# 555zapis.net
KiCad netlist of a schematic drawn in EAGLE
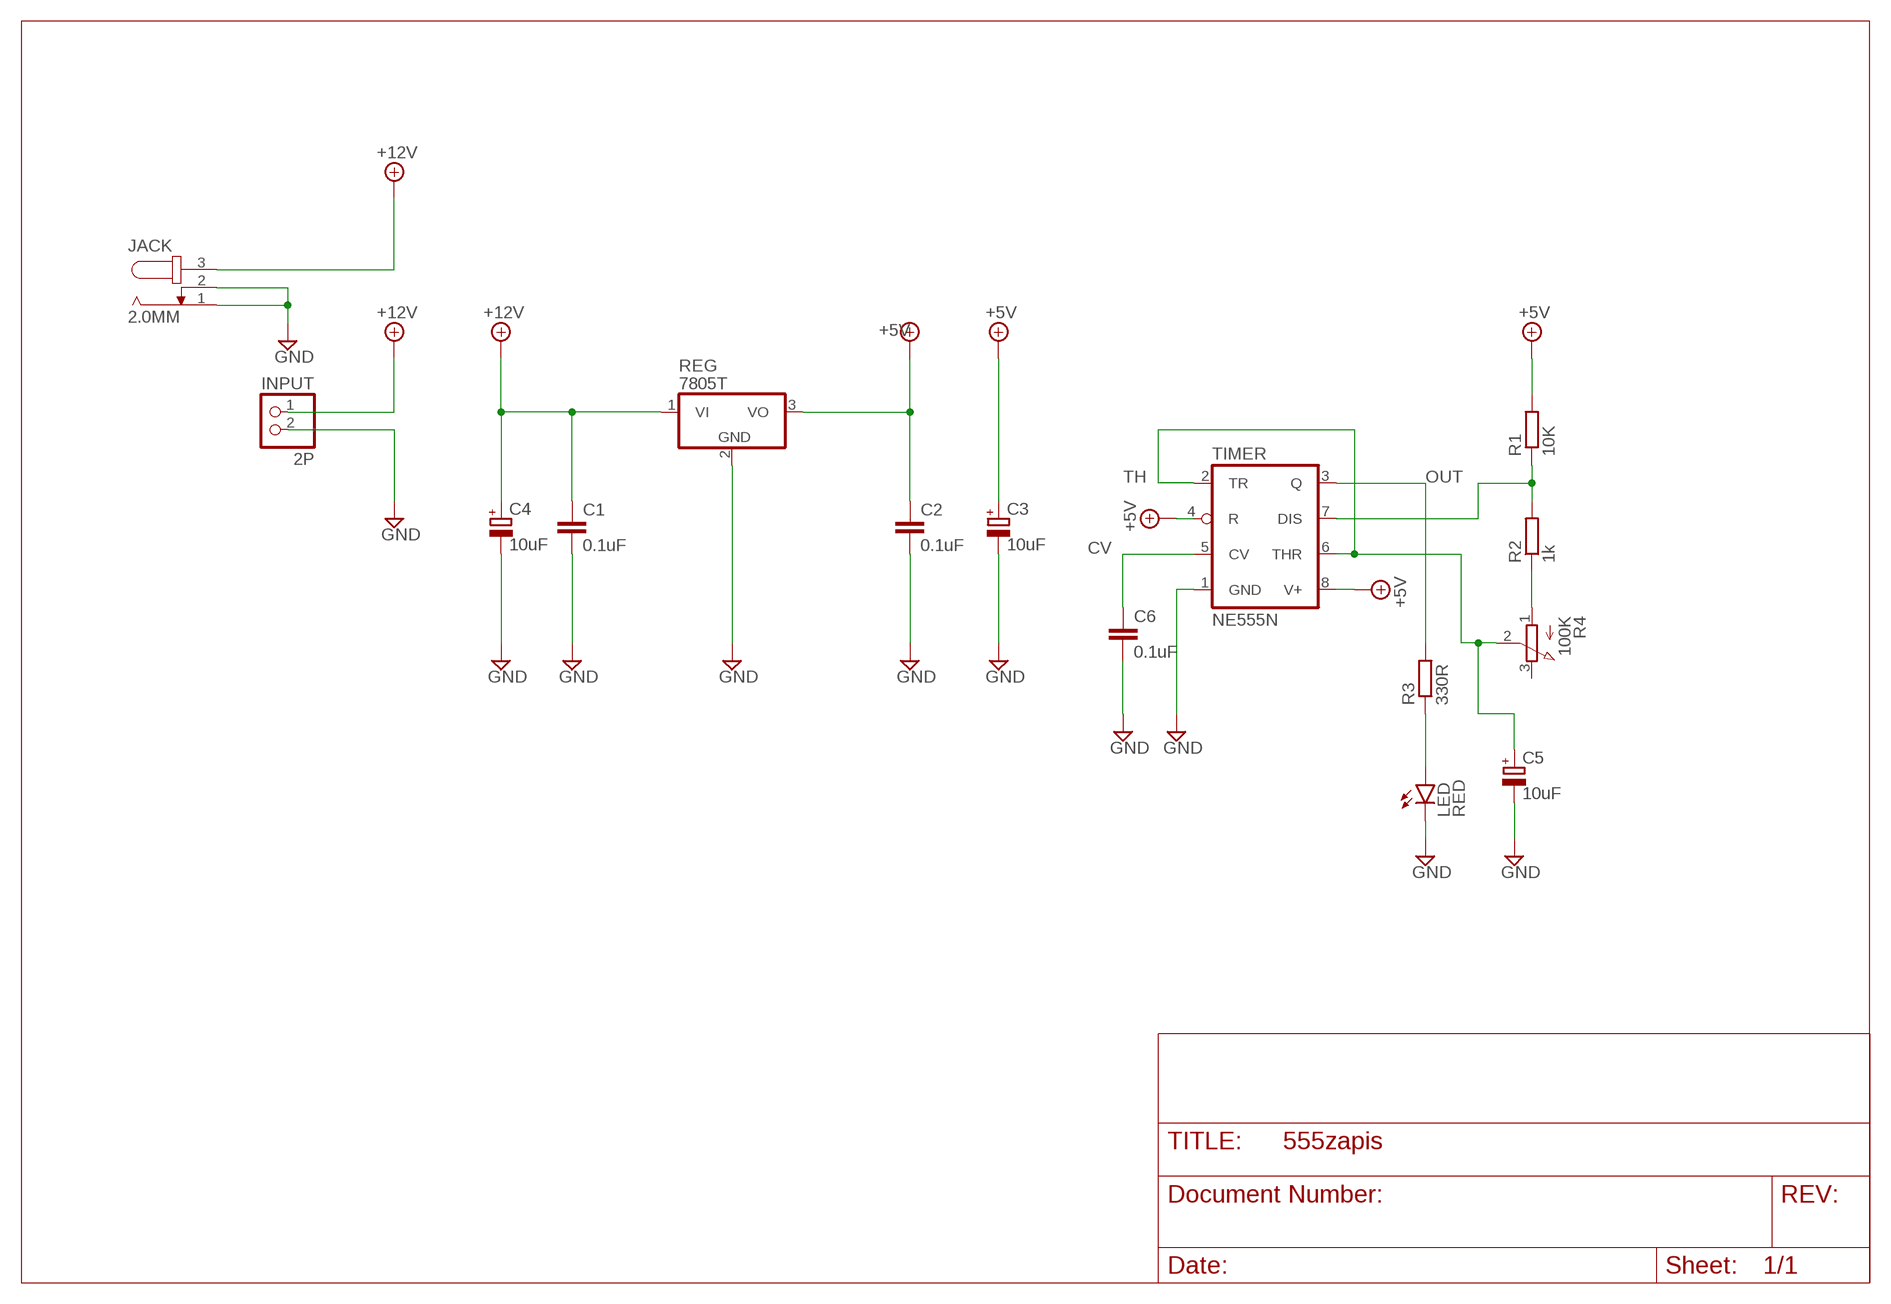
[diagram p0: schematic, sheet 1]

(export (version "E")
  (design (tool "Eeschema 10.0.6"))
  (components
    (comp (ref "C1")
      (value "0.1uF")
      (footprint "eagle-import:C050-030X075")
      (libsource (lib "eagle-import") (part "C-EU050-030X075"))
    )
    (comp (ref "C2")
      (value "0.1uF")
      (footprint "eagle-import:C050-030X075")
      (libsource (lib "eagle-import") (part "C-EU050-030X075"))
    )
    (comp (ref "C3")
      (value "10uF")
      (footprint "eagle-import:E3,5-8")
      (libsource (lib "eagle-import") (part "CPOL-EUE3.5-8"))
    )
    (comp (ref "C4")
      (value "10uF")
      (footprint "eagle-import:E3,5-8")
      (libsource (lib "eagle-import") (part "CPOL-EUE3.5-8"))
    )
    (comp (ref "C5")
      (value "10uF")
      (footprint "eagle-import:E3,5-8")
      (libsource (lib "eagle-import") (part "CPOL-EUE3.5-8"))
    )
    (comp (ref "C6")
      (value "0.1uF")
      (footprint "eagle-import:C050-030X075")
      (libsource (lib "eagle-import") (part "C-EU050-030X075"))
    )
    (comp (ref "INPUT")
      (value "2P")
      (footprint "eagle-import:1X02")
      (libsource (lib "eagle-import") (part "PINHD-1X2"))
    )
    (comp (ref "JACK")
      (value "2.0MM")
      (footprint "eagle-import:SPC4078")
      (libsource (lib "eagle-import") (part "JACK-PLUG1"))
    )
    (comp (ref "LED")
      (value "RED")
      (footprint "eagle-import:LED5MM")
      (libsource (lib "eagle-import") (part "LED5MM"))
    )
    (comp (ref "R1")
      (value "10K")
      (footprint "eagle-import:0207_10")
      (libsource (lib "eagle-import") (part "R-EU_0207/10"))
    )
    (comp (ref "R2")
      (value "1k")
      (footprint "eagle-import:0207_10")
      (libsource (lib "eagle-import") (part "R-EU_0207/10"))
    )
    (comp (ref "R3")
      (value "330R")
      (footprint "eagle-import:0207_10")
      (libsource (lib "eagle-import") (part "R-EU_0207/10"))
    )
    (comp (ref "R4")
      (value "100K")
      (footprint "eagle-import:3RP_1610N")
      (libsource (lib "eagle-import") (part "3RP/1610N"))
    )
    (comp (ref "REG")
      (value "7805T")
      (footprint "eagle-import:TO220H")
      (libsource (lib "eagle-import") (part "78T05"))
    )
    (comp (ref "TIMER")
      (value "NE555N")
      (footprint "eagle-import:DIL08")
      (libsource (lib "eagle-import") (part "555NNE"))
    )
  )
  (nets
    (net (code "1") (name "+5V") (class "Default")
      (node (ref "C2") (pin "1") (pinfunction "1_1") (pintype "passive"))
      (node (ref "C3") (pin "+") (pinfunction "+_+") (pintype "passive"))
      (node (ref "R1") (pin "2") (pinfunction "2_2") (pintype "passive"))
      (node (ref "REG") (pin "3") (pinfunction "VO_3") (pintype "passive"))
      (node (ref "TIMER") (pin "4") (pinfunction "R_4") (pintype "input"))
      (node (ref "TIMER") (pin "8") (pinfunction "V+_8") (pintype "power_in"))
    )
    (net (code "2") (name "+12V") (class "Default")
      (node (ref "C1") (pin "1") (pinfunction "1_1") (pintype "passive"))
      (node (ref "C4") (pin "+") (pinfunction "+_+") (pintype "passive"))
      (node (ref "INPUT") (pin "1") (pinfunction "1_1") (pintype "passive"))
      (node (ref "JACK") (pin "3") (pinfunction "3_3") (pintype "passive"))
      (node (ref "REG") (pin "1") (pinfunction "VI_1") (pintype "input"))
    )
    (net (code "3") (name "/CV") (class "Default")
      (node (ref "C6") (pin "1") (pinfunction "1_1") (pintype "passive"))
      (node (ref "TIMER") (pin "5") (pinfunction "CV_5") (pintype "input"))
    )
    (net (code "4") (name "/OUT") (class "Default")
      (node (ref "R3") (pin "2") (pinfunction "2_2") (pintype "passive"))
      (node (ref "TIMER") (pin "3") (pinfunction "Q_3") (pintype "output"))
    )
    (net (code "5") (name "/TH") (class "Default")
      (node (ref "C5") (pin "+") (pinfunction "+_+") (pintype "passive"))
      (node (ref "R4") (pin "2") (pinfunction "S_2") (pintype "passive"))
      (node (ref "TIMER") (pin "2") (pinfunction "TR_2") (pintype "input"))
      (node (ref "TIMER") (pin "6") (pinfunction "THR_6") (pintype "input"))
    )
    (net (code "6") (name "GND") (class "Default")
      (node (ref "C1") (pin "2") (pinfunction "2_2") (pintype "passive"))
      (node (ref "C2") (pin "2") (pinfunction "2_2") (pintype "passive"))
      (node (ref "C3") (pin "-") (pinfunction "-_-") (pintype "passive"))
      (node (ref "C4") (pin "-") (pinfunction "-_-") (pintype "passive"))
      (node (ref "C5") (pin "-") (pinfunction "-_-") (pintype "passive"))
      (node (ref "C6") (pin "2") (pinfunction "2_2") (pintype "passive"))
      (node (ref "INPUT") (pin "2") (pinfunction "2_2") (pintype "passive"))
      (node (ref "JACK") (pin "1") (pinfunction "1_1") (pintype "passive"))
      (node (ref "JACK") (pin "2") (pinfunction "2_2") (pintype "passive"))
      (node (ref "LED") (pin "K") (pinfunction "C_K") (pintype "passive"))
      (node (ref "REG") (pin "2") (pinfunction "GND_2") (pintype "passive"))
      (node (ref "TIMER") (pin "1") (pinfunction "GND_1") (pintype "power_in"))
    )
    (net (code "7") (name "Net-(LED-PadA)") (class "Default")
      (node (ref "LED") (pin "A") (pinfunction "A_A") (pintype "passive"))
      (node (ref "R3") (pin "1") (pinfunction "1_1") (pintype "passive"))
    )
    (net (code "8") (name "Net-(R4-A)") (class "Default")
      (node (ref "R2") (pin "1") (pinfunction "1_1") (pintype "passive"))
      (node (ref "R4") (pin "1") (pinfunction "A_1") (pintype "passive"))
    )
    (net (code "9") (name "Net-(TIMER-DIS)") (class "Default")
      (node (ref "R1") (pin "1") (pinfunction "1_1") (pintype "passive"))
      (node (ref "R2") (pin "2") (pinfunction "2_2") (pintype "passive"))
      (node (ref "TIMER") (pin "7") (pinfunction "DIS_7") (pintype "input"))
    )
    (net (code "10") (name "unconnected-(R4-E-Pad3)") (class "Default")
      (node (ref "R4") (pin "3") (pinfunction "E_3") (pintype "passive"))
    )
  )
)
